# trinamic-controller-dribbler.net
KiCad netlist of a schematic drawn in Altium Designer
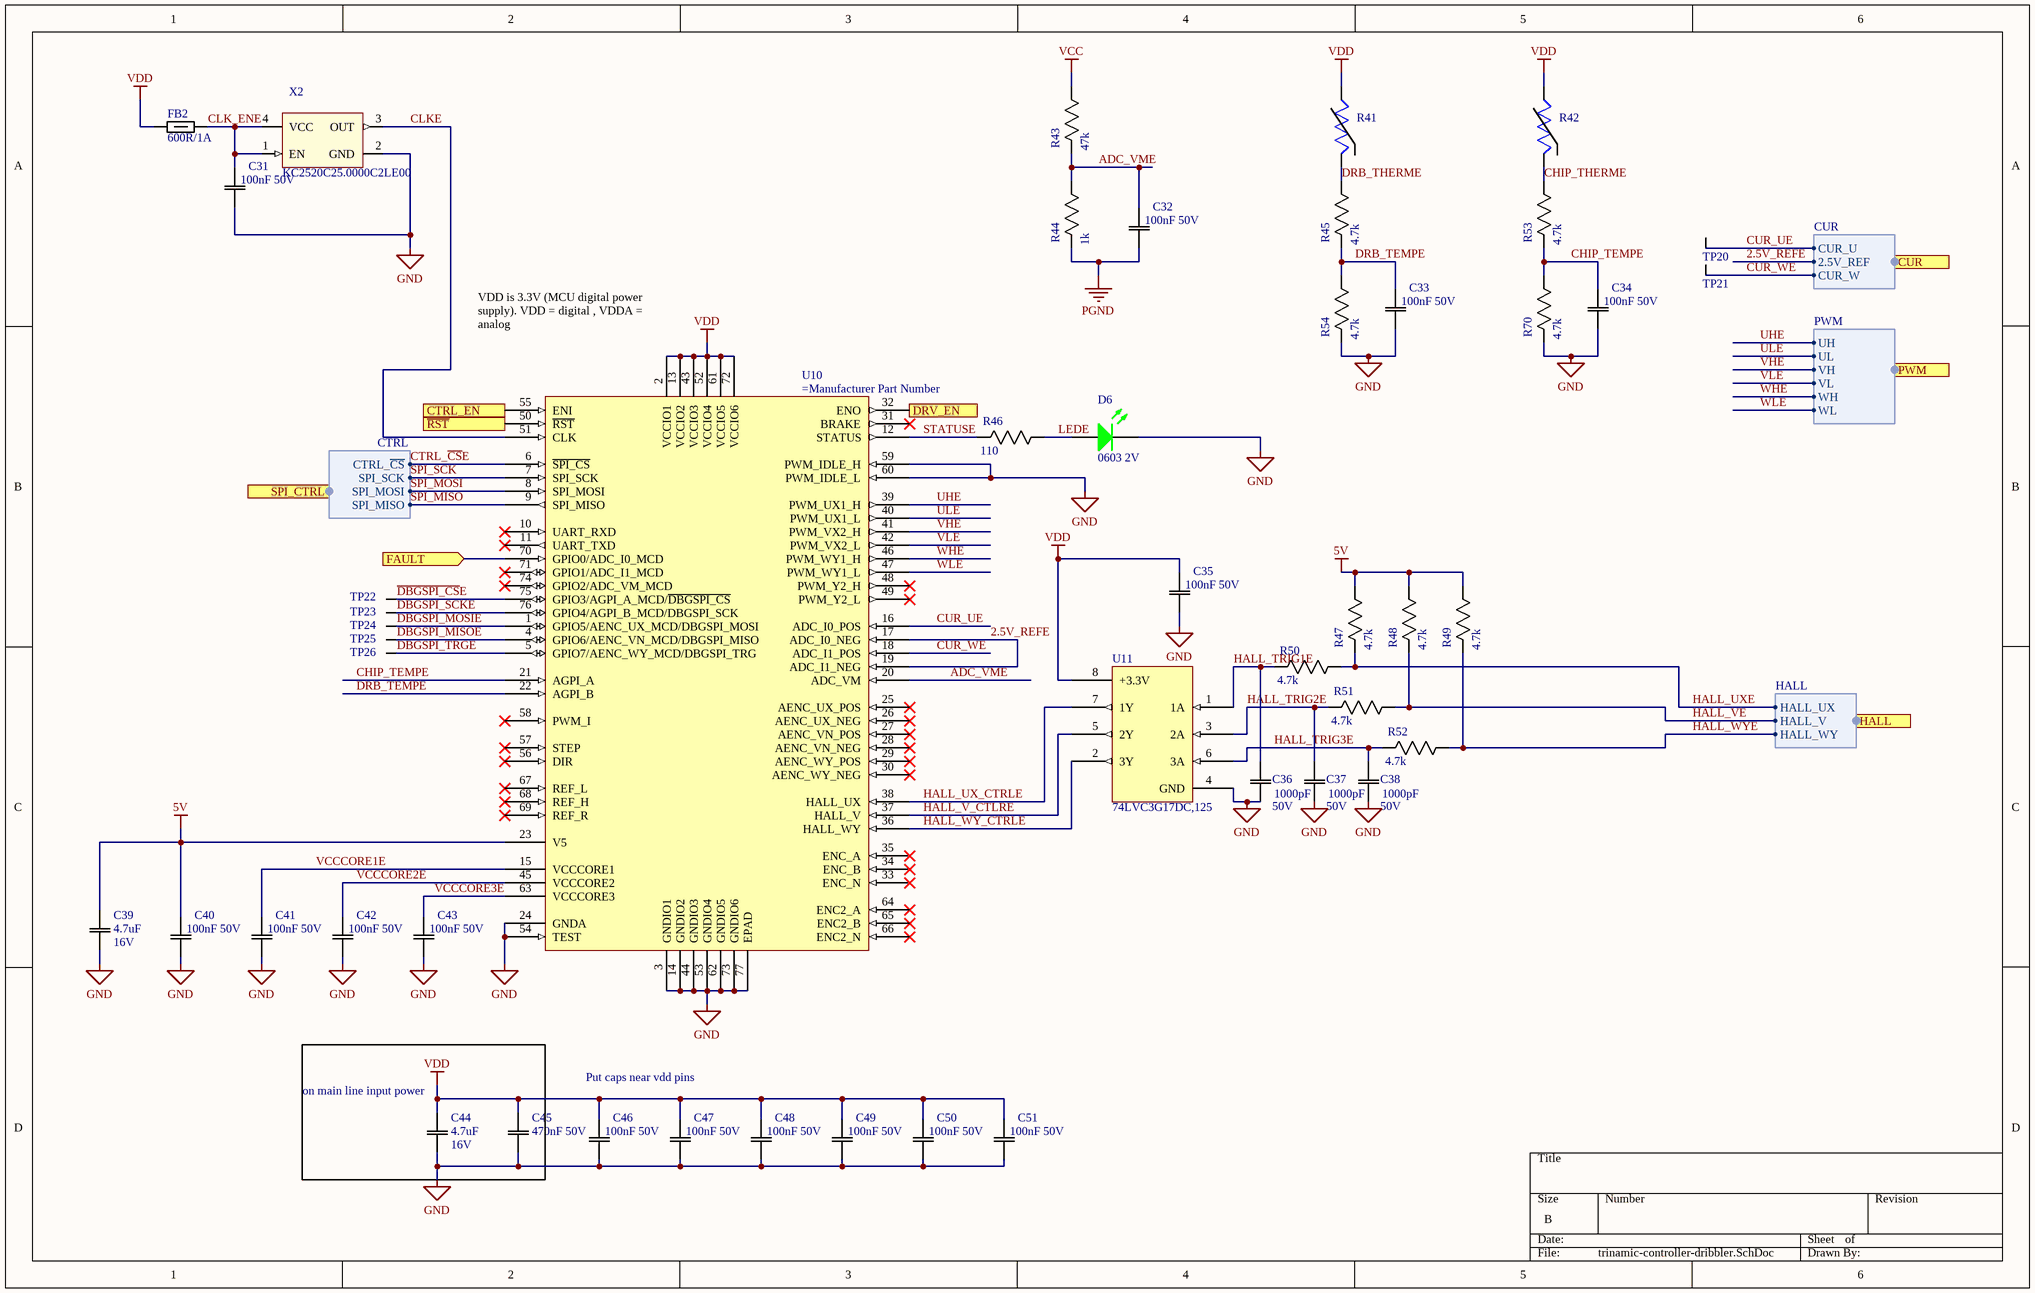
[diagram p0: trinamic-controller-dribbler.SchDoc]

(export (version "E")
  (design (tool "Eeschema 10.0.6"))
  (components
    (comp (ref "C31")
      (value "100nF 50V")
      (footprint "0603")
      (description "Default Symbol for Capacitors")
      (fields (field (name "TOLERANCE") "10%") (field (name "PART NUMBER") "CAP 100nF 50V"))
      (libsource (lib "capacitor_library") (part "CAP_Default"))
    )
    (comp (ref "C32")
      (value "100nF 50V")
      (footprint "0603")
      (description "Default Symbol for Capacitors")
      (fields (field (name "TOLERANCE") "10%") (field (name "PART NUMBER") "CAP 100nF 50V"))
      (libsource (lib "capacitor_library") (part "CAP_Default"))
    )
    (comp (ref "C33")
      (value "100nF 50V")
      (footprint "0603")
      (description "Default Symbol for Capacitors")
      (fields (field (name "TOLERANCE") "10%") (field (name "PART NUMBER") "CAP 100nF 50V"))
      (libsource (lib "capacitor_library") (part "CAP_Default"))
    )
    (comp (ref "C34")
      (value "100nF 50V")
      (footprint "0603")
      (description "Default Symbol for Capacitors")
      (fields (field (name "TOLERANCE") "10%") (field (name "PART NUMBER") "CAP 100nF 50V"))
      (libsource (lib "capacitor_library") (part "CAP_Default"))
    )
    (comp (ref "C35")
      (value "100nF 50V")
      (footprint "0603")
      (description "Default Symbol for Capacitors")
      (fields (field (name "TOLERANCE") "10%") (field (name "PART NUMBER") "CAP 100nF 50V"))
      (libsource (lib "capacitor_library") (part "CAP_Default"))
    )
    (comp (ref "C36")
      (value "1000pF")
      (footprint "0603")
      (description "Default Symbol for Capacitors")
      (fields
        (field (name "TOLERANCE") "10%")
        (field (name "RATING") "50V")
        (field (name "PART NUMBER") "CAP 1000pF 50V")
      )
      (libsource (lib "capacitor_library") (part "CAP_Default"))
    )
    (comp (ref "C37")
      (value "1000pF")
      (footprint "0603")
      (description "Default Symbol for Capacitors")
      (fields
        (field (name "TOLERANCE") "10%")
        (field (name "RATING") "50V")
        (field (name "PART NUMBER") "CAP 1000pF 50V")
      )
      (libsource (lib "capacitor_library") (part "CAP_Default"))
    )
    (comp (ref "C38")
      (value "1000pF")
      (footprint "0603")
      (description "Default Symbol for Capacitors")
      (fields
        (field (name "TOLERANCE") "10%")
        (field (name "RATING") "50V")
        (field (name "PART NUMBER") "CAP 1000pF 50V")
      )
      (libsource (lib "capacitor_library") (part "CAP_Default"))
    )
    (comp (ref "C39")
      (value "4.7uF")
      (footprint "0603")
      (description "Default Symbol for Capacitors")
      (fields
        (field (name "TOLERANCE") "10%")
        (field (name "RATING") "16V")
        (field (name "PART NUMBER") "CAP 4.7uF 16V")
      )
      (libsource (lib "capacitor_library") (part "CAP_Default"))
    )
    (comp (ref "C40")
      (value "100nF 50V")
      (footprint "0603")
      (description "Default Symbol for Capacitors")
      (fields (field (name "TOLERANCE") "10%") (field (name "PART NUMBER") "CAP 100nF 50V"))
      (libsource (lib "capacitor_library") (part "CAP_Default"))
    )
    (comp (ref "C41")
      (value "100nF 50V")
      (footprint "0603")
      (description "Default Symbol for Capacitors")
      (fields (field (name "TOLERANCE") "10%") (field (name "PART NUMBER") "CAP 100nF 50V"))
      (libsource (lib "capacitor_library") (part "CAP_Default"))
    )
    (comp (ref "C42")
      (value "100nF 50V")
      (footprint "0603")
      (description "Default Symbol for Capacitors")
      (fields (field (name "TOLERANCE") "10%") (field (name "PART NUMBER") "CAP 100nF 50V"))
      (libsource (lib "capacitor_library") (part "CAP_Default"))
    )
    (comp (ref "C43")
      (value "100nF 50V")
      (footprint "0603")
      (description "Default Symbol for Capacitors")
      (fields (field (name "TOLERANCE") "10%") (field (name "PART NUMBER") "CAP 100nF 50V"))
      (libsource (lib "capacitor_library") (part "CAP_Default"))
    )
    (comp (ref "C44")
      (value "4.7uF")
      (footprint "0603")
      (description "Default Symbol for Capacitors")
      (fields
        (field (name "TOLERANCE") "10%")
        (field (name "RATING") "16V")
        (field (name "PART NUMBER") "CAP 4.7uF 16V")
      )
      (libsource (lib "capacitor_library") (part "CAP_Default"))
    )
    (comp (ref "C45")
      (value "470nF 50V")
      (footprint "0603")
      (description "Default Symbol for Capacitors")
      (fields (field (name "TOLERANCE") "10%") (field (name "PART NUMBER") "CAP 470nF 50V"))
      (libsource (lib "capacitor_library") (part "CAP_Default"))
    )
    (comp (ref "C46")
      (value "100nF 50V")
      (footprint "0603")
      (description "Default Symbol for Capacitors")
      (fields (field (name "TOLERANCE") "10%") (field (name "PART NUMBER") "CAP 100nF 50V"))
      (libsource (lib "capacitor_library") (part "CAP_Default"))
    )
    (comp (ref "C47")
      (value "100nF 50V")
      (footprint "0603")
      (description "Default Symbol for Capacitors")
      (fields (field (name "TOLERANCE") "10%") (field (name "PART NUMBER") "CAP 100nF 50V"))
      (libsource (lib "capacitor_library") (part "CAP_Default"))
    )
    (comp (ref "C48")
      (value "100nF 50V")
      (footprint "0603")
      (description "Default Symbol for Capacitors")
      (fields (field (name "TOLERANCE") "10%") (field (name "PART NUMBER") "CAP 100nF 50V"))
      (libsource (lib "capacitor_library") (part "CAP_Default"))
    )
    (comp (ref "C49")
      (value "100nF 50V")
      (footprint "0603")
      (description "Default Symbol for Capacitors")
      (fields (field (name "TOLERANCE") "10%") (field (name "PART NUMBER") "CAP 100nF 50V"))
      (libsource (lib "capacitor_library") (part "CAP_Default"))
    )
    (comp (ref "C50")
      (value "100nF 50V")
      (footprint "0603")
      (description "Default Symbol for Capacitors")
      (fields (field (name "TOLERANCE") "10%") (field (name "PART NUMBER") "CAP 100nF 50V"))
      (libsource (lib "capacitor_library") (part "CAP_Default"))
    )
    (comp (ref "C51")
      (value "100nF 50V")
      (footprint "0603")
      (description "Default Symbol for Capacitors")
      (fields (field (name "TOLERANCE") "10%") (field (name "PART NUMBER") "CAP 100nF 50V"))
      (libsource (lib "capacitor_library") (part "CAP_Default"))
    )
    (comp (ref "D6")
      (value "0603 2V")
      (footprint "0603 - LED")
      (description "LED Uni-Color Green 574nm 2-Pin Chip LED T/R")
      (fields (field (name "PART NUMBER") "LED GREEN SMD 0603"))
      (libsource (lib "Diode_Library") (part "LED GREEN SMD 0603"))
    )
    (comp (ref "FB2")
      (value "600R/1A")
      (footprint "0603")
      (fields (field (name "PART NUMBER") "FERRITE BEAD 200 MOHM 0603 1LN"))
      (libsource (lib "Inductor_Library") (part "FERRITE BEAD 200 MOHM 0603 1LN"))
    )
    (comp (ref "R41")
      (value "RES NTC 10k")
      (footprint "THERMISTOR TH")
      (fields (field (name "PART NUMBER") "RES NTC 10k TH") (field (name "TOLERANCE") "1%"))
      (libsource (lib "Resistor_Library") (part "RES NTC 10k"))
    )
    (comp (ref "R42")
      (value "RES NTC 10k")
      (footprint "0603")
      (fields (field (name "PART NUMBER") "RES NTC 10k CHIP") (field (name "TOLERANCE") "1%"))
      (libsource (lib "Resistor_Library") (part "RES NTC 10k"))
    )
    (comp (ref "R43")
      (value "47k")
      (footprint "0603")
      (description "Default Resistor Symbol")
      (fields (field (name "TOLERANCE") "1%") (field (name "PART NUMBER") "RES 47k 1/8W - 1%"))
      (libsource (lib "") (part "RES_DEFAULT_1"))
    )
    (comp (ref "R44")
      (value "1k")
      (footprint "0603")
      (description "Default Resistor Symbol")
      (fields (field (name "TOLERANCE") "1%") (field (name "PART NUMBER") "RES 1k 1/8W - 1%"))
      (libsource (lib "Resistor_Library") (part "RES_DEFAULT"))
    )
    (comp (ref "R45")
      (value "4.7k")
      (footprint "0603")
      (description "Default Resistor Symbol")
      (fields (field (name "TOLERANCE") "1%") (field (name "PART NUMBER") "RES 4.7k 1/8W - 1%"))
      (libsource (lib "Resistor_Library") (part "RES_DEFAULT"))
    )
    (comp (ref "R46")
      (value "110")
      (footprint "0603")
      (description "Default Resistor Symbol")
      (fields (field (name "TOLERANCE") "1%") (field (name "PART NUMBER") "RES 110.0 1/8W - 1%"))
      (libsource (lib "") (part "RES_DEFAULT_2"))
    )
    (comp (ref "R47")
      (value "4.7k")
      (footprint "0603")
      (description "Default Resistor Symbol")
      (fields (field (name "TOLERANCE") "5%") (field (name "PART NUMBER") "RES 4.7k 1/8W - 5%"))
      (libsource (lib "") (part "RES_DEFAULT_2"))
    )
    (comp (ref "R48")
      (value "4.7k")
      (footprint "0603")
      (description "Default Resistor Symbol")
      (fields (field (name "TOLERANCE") "5%") (field (name "PART NUMBER") "RES 4.7k 1/8W - 5%"))
      (libsource (lib "") (part "RES_DEFAULT_2"))
    )
    (comp (ref "R49")
      (value "4.7k")
      (footprint "0603")
      (description "Default Resistor Symbol")
      (fields (field (name "TOLERANCE") "5%") (field (name "PART NUMBER") "RES 4.7k 1/8W - 5%"))
      (libsource (lib "Resistor_Library") (part "RES_DEFAULT"))
    )
    (comp (ref "R50")
      (value "4.7k")
      (footprint "0603")
      (description "Default Resistor Symbol")
      (fields (field (name "TOLERANCE") "5%") (field (name "PART NUMBER") "RES 4.7k 1/8W - 5%"))
      (libsource (lib "") (part "RES_DEFAULT_2"))
    )
    (comp (ref "R51")
      (value "4.7k")
      (footprint "0603")
      (description "Default Resistor Symbol")
      (fields (field (name "TOLERANCE") "5%") (field (name "PART NUMBER") "RES 4.7k 1/8W - 5%"))
      (libsource (lib "") (part "RES_DEFAULT_2"))
    )
    (comp (ref "R52")
      (value "4.7k")
      (footprint "0603")
      (description "Default Resistor Symbol")
      (fields (field (name "TOLERANCE") "5%") (field (name "PART NUMBER") "RES 4.7k 1/8W - 5%"))
      (libsource (lib "") (part "RES_DEFAULT_2"))
    )
    (comp (ref "R53")
      (value "4.7k")
      (footprint "0603")
      (description "Default Resistor Symbol")
      (fields (field (name "TOLERANCE") "1%") (field (name "PART NUMBER") "RES 4.7k 1/8W - 1%"))
      (libsource (lib "Resistor_Library") (part "RES_DEFAULT"))
    )
    (comp (ref "R54")
      (value "4.7k")
      (footprint "0603")
      (description "Default Resistor Symbol")
      (fields (field (name "TOLERANCE") "1%") (field (name "PART NUMBER") "RES 4.7k 1/8W - 1%"))
      (libsource (lib "Resistor_Library") (part "RES_DEFAULT"))
    )
    (comp (ref "R70")
      (value "4.7k")
      (footprint "0603")
      (description "Default Resistor Symbol")
      (fields (field (name "TOLERANCE") "1%") (field (name "PART NUMBER") "RES 4.7k 1/8W - 1%"))
      (libsource (lib "Resistor_Library") (part "RES_DEFAULT"))
    )
    (comp (ref "TP20")
      (value "C_UE")
      (footprint "TP")
      (fields (field (name "PART NUMBER") "Test Point (Via)"))
      (libsource (lib "IC_Library") (part "Test Point (Via)"))
    )
    (comp (ref "TP21")
      (value "C_WE")
      (footprint "TP")
      (fields (field (name "PART NUMBER") "Test Point (Via)"))
      (libsource (lib "IC_Library") (part "Test Point (Via)"))
    )
    (comp (ref "TP22")
      (value "DBG_CS")
      (footprint "TP")
      (fields (field (name "PART NUMBER") "Test Point (Via)"))
      (libsource (lib "IC_Library") (part "Test Point (Via)"))
    )
    (comp (ref "TP23")
      (value "DBG_SCK")
      (footprint "TP")
      (fields (field (name "PART NUMBER") "Test Point (Via)"))
      (libsource (lib "IC_Library") (part "Test Point (Via)"))
    )
    (comp (ref "TP24")
      (value "DBG_MOSI")
      (footprint "TP")
      (fields (field (name "PART NUMBER") "Test Point (Via)"))
      (libsource (lib "IC_Library") (part "Test Point (Via)"))
    )
    (comp (ref "TP25")
      (value "DBG_MISO")
      (footprint "TP")
      (fields (field (name "PART NUMBER") "Test Point (Via)"))
      (libsource (lib "IC_Library") (part "Test Point (Via)"))
    )
    (comp (ref "TP26")
      (value "DBG_TRG")
      (footprint "TP")
      (fields (field (name "PART NUMBER") "Test Point (Via)"))
      (libsource (lib "IC_Library") (part "Test Point (Via)"))
    )
    (comp (ref "U10")
      (value "~")
      (footprint "QFN40P1050X650X90_HS-77N")
      (description "Motor Driver, -40 To 125Deg C Rohs Compliant: Yes")
      (fields (field (name "PART NUMBER") "TMC4671"))
      (libsource (lib "IC_Library") (part "TMC4671"))
    )
    (comp (ref "U11")
      (value "74LVC3G17DC,125")
      (footprint "8-VSSOP")
      (description "IC BUFFER TRIPLE SCHMITT TRIGGER 5.5V VSSOP-8")
      (fields (field (name "PART NUMBER") "IC 74LVC3G17DC,125"))
      (libsource (lib "IC_Library") (part "IC 74LVC3G17DC,125"))
    )
    (comp (ref "X2")
      (value "KC2520C25.0000C2LE00")
      (footprint "KC2520C25.0000C2LE00")
      (description "Oscillator XO 25MHz ±15ppm 15pF CMOS 55% 2.5V/3.3V 4-Pin Mini-CSMD T/R")
      (fields (field (name "PART NUMBER") "XTAL OSC 25MHz 3.3V"))
      (libsource (lib "Oscillator_Library") (part "XTAL OSC 25MHz 3.3V"))
    )
  )
  (nets
    (net (code "5") (name "/2.5V_REFE") (class "Default")
      (node (ref "U10") (pin "17") (pinfunction "ADC_I0_NEG_17") (pintype "input"))
      (node (ref "U10") (pin "19") (pinfunction "ADC_I1_NEG_19") (pintype "input"))
    )
    (net (code "6") (name "/ADC_VME") (class "Default")
      (node (ref "C32") (pin "2") (pinfunction "C2_2") (pintype "passive"))
      (node (ref "R43") (pin "2") (pinfunction "R2_2") (pintype "passive"))
      (node (ref "R44") (pin "1") (pinfunction "R1_1") (pintype "passive"))
      (node (ref "U10") (pin "20") (pinfunction "ADC_VM_20") (pintype "input"))
    )
    (net (code "7") (name "/CHIP_TEMPE") (class "Default")
      (node (ref "C34") (pin "2") (pinfunction "C2_2") (pintype "passive"))
      (node (ref "R53") (pin "2") (pinfunction "R2_2") (pintype "passive"))
      (node (ref "R70") (pin "1") (pinfunction "R1_1") (pintype "passive"))
      (node (ref "U10") (pin "21") (pinfunction "AGPI_A_21") (pintype "input"))
    )
    (net (code "8") (name "/CHIP_THERME") (class "Default")
      (node (ref "R42") (pin "1") (pinfunction "1_1") (pintype "passive"))
      (node (ref "R53") (pin "1") (pinfunction "R1_1") (pintype "passive"))
    )
    (net (code "9") (name "/CLKE") (class "Default")
      (node (ref "U10") (pin "51") (pinfunction "CLK_51") (pintype "input"))
      (node (ref "X2") (pin "3") (pinfunction "OUT_3") (pintype "output"))
    )
    (net (code "10") (name "/CLK_ENE") (class "Default")
      (node (ref "C31") (pin "2") (pinfunction "C2_2") (pintype "passive"))
      (node (ref "FB2") (pin "2") (pinfunction "2_2") (pintype "passive"))
      (node (ref "X2") (pin "1") (pinfunction "EN_1") (pintype "input"))
      (node (ref "X2") (pin "4") (pinfunction "VCC_4") (pintype "power_in"))
    )
    (net (code "11") (name "/CTRL_EN") (class "Default")
      (node (ref "U10") (pin "55") (pinfunction "ENI_55") (pintype "input"))
    )
    (net (code "12") (name "/CTRL_~{CS}E") (class "Default")
      (node (ref "U10") (pin "6") (pinfunction "~{SPI_CS}_6") (pintype "input"))
    )
    (net (code "13") (name "/CUR_UE") (class "Default")
      (node (ref "TP20") (pin "1") (pinfunction "1_1") (pintype "passive"))
      (node (ref "U10") (pin "16") (pinfunction "ADC_I0_POS_16") (pintype "input"))
    )
    (net (code "14") (name "/CUR_WE") (class "Default")
      (node (ref "TP21") (pin "1") (pinfunction "1_1") (pintype "passive"))
      (node (ref "U10") (pin "18") (pinfunction "ADC_I1_POS_18") (pintype "input"))
    )
    (net (code "15") (name "/DBGSPI_MISOE") (class "Default")
      (node (ref "TP25") (pin "1") (pinfunction "1_1") (pintype "passive"))
      (node (ref "U10") (pin "4") (pinfunction "GPIO6/AENC_VN_MCD/DBGSPI_MISO_4") (pintype "bidirectional"))
    )
    (net (code "16") (name "/DBGSPI_MOSIE") (class "Default")
      (node (ref "TP24") (pin "1") (pinfunction "1_1") (pintype "passive"))
      (node (ref "U10") (pin "1") (pinfunction "GPIO5/AENC_UX_MCD/DBGSPI_MOSI_1") (pintype "bidirectional"))
    )
    (net (code "17") (name "/DBGSPI_SCKE") (class "Default")
      (node (ref "TP23") (pin "1") (pinfunction "1_1") (pintype "passive"))
      (node (ref "U10") (pin "76") (pinfunction "GPIO4/AGPI_B_MCD/DBGSPI_SCK_76") (pintype "bidirectional"))
    )
    (net (code "18") (name "/DBGSPI_TRGE") (class "Default")
      (node (ref "TP26") (pin "1") (pinfunction "1_1") (pintype "passive"))
      (node (ref "U10") (pin "5") (pinfunction "GPIO7/AENC_WY_MCD/DBGSPI_TRG_5") (pintype "bidirectional"))
    )
    (net (code "19") (name "/DRB_TEMPE") (class "Default")
      (node (ref "C33") (pin "2") (pinfunction "C2_2") (pintype "passive"))
      (node (ref "R45") (pin "2") (pinfunction "R2_2") (pintype "passive"))
      (node (ref "R54") (pin "1") (pinfunction "R1_1") (pintype "passive"))
      (node (ref "U10") (pin "22") (pinfunction "AGPI_B_22") (pintype "input"))
    )
    (net (code "20") (name "/DRB_THERME") (class "Default")
      (node (ref "R41") (pin "1") (pinfunction "1_1") (pintype "passive"))
      (node (ref "R45") (pin "1") (pinfunction "R1_1") (pintype "passive"))
    )
    (net (code "21") (name "/DRV_EN") (class "Default")
      (node (ref "U10") (pin "32") (pinfunction "ENO_32") (pintype "output"))
    )
    (net (code "22") (name "/FAULT") (class "Default")
      (node (ref "U10") (pin "70") (pinfunction "GPIO0/ADC_I0_MCD_70") (pintype "input"))
    )
    (net (code "23") (name "/HALL_TRIG1E") (class "Default")
      (node (ref "C36") (pin "2") (pinfunction "C2_2") (pintype "passive"))
      (node (ref "R50") (pin "2") (pinfunction "R2_2") (pintype "passive"))
      (node (ref "U11") (pin "1") (pinfunction "1A_1") (pintype "input"))
    )
    (net (code "24") (name "/HALL_TRIG2E") (class "Default")
      (node (ref "C37") (pin "2") (pinfunction "C2_2") (pintype "passive"))
      (node (ref "R51") (pin "2") (pinfunction "R2_2") (pintype "passive"))
      (node (ref "U11") (pin "3") (pinfunction "2A_3") (pintype "input"))
    )
    (net (code "25") (name "/HALL_TRIG3E") (class "Default")
      (node (ref "C38") (pin "2") (pinfunction "C2_2") (pintype "passive"))
      (node (ref "R52") (pin "2") (pinfunction "R2_2") (pintype "passive"))
      (node (ref "U11") (pin "6") (pinfunction "3A_6") (pintype "input"))
    )
    (net (code "26") (name "/HALL_UXE") (class "Default")
      (node (ref "R47") (pin "2") (pinfunction "R2_2") (pintype "passive"))
      (node (ref "R50") (pin "1") (pinfunction "R1_1") (pintype "passive"))
    )
    (net (code "27") (name "/HALL_UX_CTRLE") (class "Default")
      (node (ref "U10") (pin "38") (pinfunction "HALL_UX_38") (pintype "input"))
      (node (ref "U11") (pin "7") (pinfunction "1Y_7") (pintype "output"))
    )
    (net (code "28") (name "/HALL_VE") (class "Default")
      (node (ref "R48") (pin "2") (pinfunction "R2_2") (pintype "passive"))
      (node (ref "R51") (pin "1") (pinfunction "R1_1") (pintype "passive"))
    )
    (net (code "29") (name "/HALL_V_CTLRE") (class "Default")
      (node (ref "U10") (pin "37") (pinfunction "HALL_V_37") (pintype "input"))
      (node (ref "U11") (pin "5") (pinfunction "2Y_5") (pintype "output"))
    )
    (net (code "30") (name "/HALL_WYE") (class "Default")
      (node (ref "R49") (pin "2") (pinfunction "R2_2") (pintype "passive"))
      (node (ref "R52") (pin "1") (pinfunction "R1_1") (pintype "passive"))
    )
    (net (code "31") (name "/HALL_WY_CTRLE") (class "Default")
      (node (ref "U10") (pin "36") (pinfunction "HALL_WY_36") (pintype "input"))
      (node (ref "U11") (pin "2") (pinfunction "3Y_2") (pintype "output"))
    )
    (net (code "32") (name "/LEDE") (class "Default")
      (node (ref "D6") (pin "1") (pinfunction "A_1") (pintype "passive"))
      (node (ref "R46") (pin "1") (pinfunction "R1_1") (pintype "passive"))
    )
    (net (code "33") (name "/SPI_MISO") (class "Default")
      (node (ref "U10") (pin "9") (pinfunction "SPI_MISO_9") (pintype "output"))
    )
    (net (code "34") (name "/SPI_MOSI") (class "Default")
      (node (ref "U10") (pin "8") (pinfunction "SPI_MOSI_8") (pintype "input"))
    )
    (net (code "35") (name "/SPI_SCK") (class "Default")
      (node (ref "U10") (pin "7") (pinfunction "SPI_SCK_7") (pintype "input"))
    )
    (net (code "36") (name "/STATUSE") (class "Default")
      (node (ref "R46") (pin "2") (pinfunction "R2_2") (pintype "passive"))
      (node (ref "U10") (pin "12") (pinfunction "STATUS_12") (pintype "output"))
    )
    (net (code "37") (name "/UHE") (class "Default")
      (node (ref "U10") (pin "39") (pinfunction "PWM_UX1_H_39") (pintype "output"))
    )
    (net (code "38") (name "/ULE") (class "Default")
      (node (ref "U10") (pin "40") (pinfunction "PWM_UX1_L_40") (pintype "output"))
    )
    (net (code "39") (name "/VCCCORE1E") (class "Default")
      (node (ref "C41") (pin "2") (pinfunction "C2_2") (pintype "passive"))
      (node (ref "U10") (pin "15") (pinfunction "VCCCORE1_15") (pintype "power_in"))
    )
    (net (code "40") (name "/VCCCORE2E") (class "Default")
      (node (ref "C42") (pin "2") (pinfunction "C2_2") (pintype "passive"))
      (node (ref "U10") (pin "45") (pinfunction "VCCCORE2_45") (pintype "power_in"))
    )
    (net (code "41") (name "/VCCCORE3E") (class "Default")
      (node (ref "C43") (pin "2") (pinfunction "C2_2") (pintype "passive"))
      (node (ref "U10") (pin "63") (pinfunction "VCCCORE3_63") (pintype "power_in"))
    )
    (net (code "42") (name "/VHE") (class "Default")
      (node (ref "U10") (pin "41") (pinfunction "PWM_VX2_H_41") (pintype "output"))
    )
    (net (code "43") (name "/VLE") (class "Default")
      (node (ref "U10") (pin "42") (pinfunction "PWM_VX2_L_42") (pintype "output"))
    )
    (net (code "44") (name "/WHE") (class "Default")
      (node (ref "U10") (pin "46") (pinfunction "PWM_WY1_H_46") (pintype "output"))
    )
    (net (code "45") (name "/WLE") (class "Default")
      (node (ref "U10") (pin "47") (pinfunction "PWM_WY1_L_47") (pintype "output"))
    )
    (net (code "50") (name "/~{DBGSPI_CS}E") (class "Default")
      (node (ref "TP22") (pin "1") (pinfunction "1_1") (pintype "passive"))
      (node (ref "U10") (pin "75") (pinfunction "GPIO3/AGPI_A_MCD/~{DBGSPI_CS}_75") (pintype "bidirectional"))
    )
    (net (code "51") (name "/~{RST}") (class "Default")
      (node (ref "U10") (pin "50") (pinfunction "~{RST}_50") (pintype "input"))
    )
    (net (code "52") (name "5V") (class "Default")
      (node (ref "C39") (pin "2") (pinfunction "C2_2") (pintype "passive"))
      (node (ref "C40") (pin "2") (pinfunction "C2_2") (pintype "passive"))
      (node (ref "R47") (pin "1") (pinfunction "R1_1") (pintype "passive"))
      (node (ref "R48") (pin "1") (pinfunction "R1_1") (pintype "passive"))
      (node (ref "R49") (pin "1") (pinfunction "R1_1") (pintype "passive"))
      (node (ref "U10") (pin "23") (pinfunction "V5_23") (pintype "power_in"))
    )
    (net (code "53") (name "GND") (class "Default")
      (node (ref "C31") (pin "1") (pinfunction "C1_1") (pintype "passive"))
      (node (ref "C33") (pin "1") (pinfunction "C1_1") (pintype "passive"))
      (node (ref "C34") (pin "1") (pinfunction "C1_1") (pintype "passive"))
      (node (ref "C35") (pin "1") (pinfunction "C1_1") (pintype "passive"))
      (node (ref "C36") (pin "1") (pinfunction "C1_1") (pintype "passive"))
      (node (ref "C37") (pin "1") (pinfunction "C1_1") (pintype "passive"))
      (node (ref "C38") (pin "1") (pinfunction "C1_1") (pintype "passive"))
      (node (ref "C39") (pin "1") (pinfunction "C1_1") (pintype "passive"))
      (node (ref "C40") (pin "1") (pinfunction "C1_1") (pintype "passive"))
      (node (ref "C41") (pin "1") (pinfunction "C1_1") (pintype "passive"))
      (node (ref "C42") (pin "1") (pinfunction "C1_1") (pintype "passive"))
      (node (ref "C43") (pin "1") (pinfunction "C1_1") (pintype "passive"))
      (node (ref "C44") (pin "1") (pinfunction "C1_1") (pintype "passive"))
      (node (ref "C45") (pin "1") (pinfunction "C1_1") (pintype "passive"))
      (node (ref "C46") (pin "1") (pinfunction "C1_1") (pintype "passive"))
      (node (ref "C47") (pin "1") (pinfunction "C1_1") (pintype "passive"))
      (node (ref "C48") (pin "1") (pinfunction "C1_1") (pintype "passive"))
      (node (ref "C49") (pin "1") (pinfunction "C1_1") (pintype "passive"))
      (node (ref "C50") (pin "1") (pinfunction "C1_1") (pintype "passive"))
      (node (ref "C51") (pin "1") (pinfunction "C1_1") (pintype "passive"))
      (node (ref "D6") (pin "2") (pinfunction "K_2") (pintype "passive"))
      (node (ref "R54") (pin "2") (pinfunction "R2_2") (pintype "passive"))
      (node (ref "R70") (pin "2") (pinfunction "R2_2") (pintype "passive"))
      (node (ref "U10") (pin "14") (pinfunction "GNDIO2_14") (pintype "power_in"))
      (node (ref "U10") (pin "24") (pinfunction "GNDA_24") (pintype "power_in"))
      (node (ref "U10") (pin "3") (pinfunction "GNDIO1_3") (pintype "power_in"))
      (node (ref "U10") (pin "44") (pinfunction "GNDIO3_44") (pintype "power_in"))
      (node (ref "U10") (pin "53") (pinfunction "GNDIO4_53") (pintype "power_in"))
      (node (ref "U10") (pin "54") (pinfunction "TEST_54") (pintype "input"))
      (node (ref "U10") (pin "59") (pinfunction "PWM_IDLE_H_59") (pintype "input"))
      (node (ref "U10") (pin "60") (pinfunction "PWM_IDLE_L_60") (pintype "input"))
      (node (ref "U10") (pin "62") (pinfunction "GNDIO5_62") (pintype "power_in"))
      (node (ref "U10") (pin "73") (pinfunction "GNDIO6_73") (pintype "power_in"))
      (node (ref "U10") (pin "77") (pinfunction "EPAD_77") (pintype "passive"))
      (node (ref "U11") (pin "4") (pinfunction "GND_4") (pintype "power_in"))
      (node (ref "X2") (pin "2") (pinfunction "GND_2") (pintype "power_in"))
    )
    (net (code "54") (name "PGND") (class "Default")
      (node (ref "C32") (pin "1") (pinfunction "C1_1") (pintype "passive"))
      (node (ref "R44") (pin "2") (pinfunction "R2_2") (pintype "passive"))
    )
    (net (code "55") (name "VCC") (class "Default")
      (node (ref "R43") (pin "1") (pinfunction "R1_1") (pintype "passive"))
    )
    (net (code "56") (name "VDD") (class "Default")
      (node (ref "C35") (pin "2") (pinfunction "C2_2") (pintype "passive"))
      (node (ref "C44") (pin "2") (pinfunction "C2_2") (pintype "passive"))
      (node (ref "C45") (pin "2") (pinfunction "C2_2") (pintype "passive"))
      (node (ref "C46") (pin "2") (pinfunction "C2_2") (pintype "passive"))
      (node (ref "C47") (pin "2") (pinfunction "C2_2") (pintype "passive"))
      (node (ref "C48") (pin "2") (pinfunction "C2_2") (pintype "passive"))
      (node (ref "C49") (pin "2") (pinfunction "C2_2") (pintype "passive"))
      (node (ref "C50") (pin "2") (pinfunction "C2_2") (pintype "passive"))
      (node (ref "C51") (pin "2") (pinfunction "C2_2") (pintype "passive"))
      (node (ref "FB2") (pin "1") (pinfunction "1_1") (pintype "passive"))
      (node (ref "R41") (pin "2") (pinfunction "2_2") (pintype "passive"))
      (node (ref "R42") (pin "2") (pinfunction "2_2") (pintype "passive"))
      (node (ref "U10") (pin "13") (pinfunction "VCCIO2_13") (pintype "power_in"))
      (node (ref "U10") (pin "2") (pinfunction "VCCIO1_2") (pintype "power_in"))
      (node (ref "U10") (pin "43") (pinfunction "VCCIO3_43") (pintype "power_in"))
      (node (ref "U10") (pin "52") (pinfunction "VCCIO4_52") (pintype "power_in"))
      (node (ref "U10") (pin "61") (pinfunction "VCCIO5_61") (pintype "power_in"))
      (node (ref "U10") (pin "72") (pinfunction "VCCIO6_72") (pintype "power_in"))
      (node (ref "U11") (pin "8") (pinfunction "+3.3V_8") (pintype "power_in"))
    )
    (net (code "57") (name "unconnected-(U10-AENC_UX_NEG-Pad26)") (class "Default")
      (node (ref "U10") (pin "26") (pinfunction "AENC_UX_NEG_26") (pintype "input+no_connect"))
    )
    (net (code "58") (name "unconnected-(U10-AENC_UX_POS-Pad25)") (class "Default")
      (node (ref "U10") (pin "25") (pinfunction "AENC_UX_POS_25") (pintype "input+no_connect"))
    )
    (net (code "59") (name "unconnected-(U10-AENC_VN_NEG-Pad28)") (class "Default")
      (node (ref "U10") (pin "28") (pinfunction "AENC_VN_NEG_28") (pintype "input+no_connect"))
    )
    (net (code "60") (name "unconnected-(U10-AENC_VN_POS-Pad27)") (class "Default")
      (node (ref "U10") (pin "27") (pinfunction "AENC_VN_POS_27") (pintype "input+no_connect"))
    )
    (net (code "61") (name "unconnected-(U10-AENC_WY_NEG-Pad30)") (class "Default")
      (node (ref "U10") (pin "30") (pinfunction "AENC_WY_NEG_30") (pintype "input+no_connect"))
    )
    (net (code "62") (name "unconnected-(U10-AENC_WY_POS-Pad29)") (class "Default")
      (node (ref "U10") (pin "29") (pinfunction "AENC_WY_POS_29") (pintype "input+no_connect"))
    )
    (net (code "63") (name "unconnected-(U10-BRAKE-Pad31)") (class "Default")
      (node (ref "U10") (pin "31") (pinfunction "BRAKE_31") (pintype "output+no_connect"))
    )
    (net (code "64") (name "unconnected-(U10-DIR-Pad56)") (class "Default")
      (node (ref "U10") (pin "56") (pinfunction "DIR_56") (pintype "input+no_connect"))
    )
    (net (code "65") (name "unconnected-(U10-ENC2_A-Pad64)") (class "Default")
      (node (ref "U10") (pin "64") (pinfunction "ENC2_A_64") (pintype "input+no_connect"))
    )
    (net (code "66") (name "unconnected-(U10-ENC2_B-Pad65)") (class "Default")
      (node (ref "U10") (pin "65") (pinfunction "ENC2_B_65") (pintype "input+no_connect"))
    )
    (net (code "67") (name "unconnected-(U10-ENC2_N-Pad66)") (class "Default")
      (node (ref "U10") (pin "66") (pinfunction "ENC2_N_66") (pintype "input+no_connect"))
    )
    (net (code "68") (name "unconnected-(U10-ENC_A-Pad35)") (class "Default")
      (node (ref "U10") (pin "35") (pinfunction "ENC_A_35") (pintype "input+no_connect"))
    )
    (net (code "69") (name "unconnected-(U10-ENC_B-Pad34)") (class "Default")
      (node (ref "U10") (pin "34") (pinfunction "ENC_B_34") (pintype "input+no_connect"))
    )
    (net (code "70") (name "unconnected-(U10-ENC_N-Pad33)") (class "Default")
      (node (ref "U10") (pin "33") (pinfunction "ENC_N_33") (pintype "input+no_connect"))
    )
    (net (code "71") (name "unconnected-(U10-GPIO1{slash}ADC_I1_MCD-Pad71)") (class "Default")
      (node (ref "U10") (pin "71") (pinfunction "GPIO1/ADC_I1_MCD_71") (pintype "bidirectional+no_connect"))
    )
    (net (code "72") (name "unconnected-(U10-GPIO2{slash}ADC_VM_MCD-Pad74)") (class "Default")
      (node (ref "U10") (pin "74") (pinfunction "GPIO2/ADC_VM_MCD_74") (pintype "bidirectional+no_connect"))
    )
    (net (code "73") (name "unconnected-(U10-PWM_I-Pad58)") (class "Default")
      (node (ref "U10") (pin "58") (pinfunction "PWM_I_58") (pintype "input+no_connect"))
    )
    (net (code "74") (name "unconnected-(U10-PWM_Y2_H-Pad48)") (class "Default")
      (node (ref "U10") (pin "48") (pinfunction "PWM_Y2_H_48") (pintype "output+no_connect"))
    )
    (net (code "75") (name "unconnected-(U10-PWM_Y2_L-Pad49)") (class "Default")
      (node (ref "U10") (pin "49") (pinfunction "PWM_Y2_L_49") (pintype "output+no_connect"))
    )
    (net (code "76") (name "unconnected-(U10-REF_H-Pad68)") (class "Default")
      (node (ref "U10") (pin "68") (pinfunction "REF_H_68") (pintype "input+no_connect"))
    )
    (net (code "77") (name "unconnected-(U10-REF_L-Pad67)") (class "Default")
      (node (ref "U10") (pin "67") (pinfunction "REF_L_67") (pintype "input+no_connect"))
    )
    (net (code "78") (name "unconnected-(U10-REF_R-Pad69)") (class "Default")
      (node (ref "U10") (pin "69") (pinfunction "REF_R_69") (pintype "input+no_connect"))
    )
    (net (code "79") (name "unconnected-(U10-STEP-Pad57)") (class "Default")
      (node (ref "U10") (pin "57") (pinfunction "STEP_57") (pintype "input+no_connect"))
    )
    (net (code "80") (name "unconnected-(U10-UART_RXD-Pad10)") (class "Default")
      (node (ref "U10") (pin "10") (pinfunction "UART_RXD_10") (pintype "input+no_connect"))
    )
    (net (code "81") (name "unconnected-(U10-UART_TXD-Pad11)") (class "Default")
      (node (ref "U10") (pin "11") (pinfunction "UART_TXD_11") (pintype "output+no_connect"))
    )
  )
)
